# eth_part.net
KiCad netlist of a schematic drawn in Altium Designer
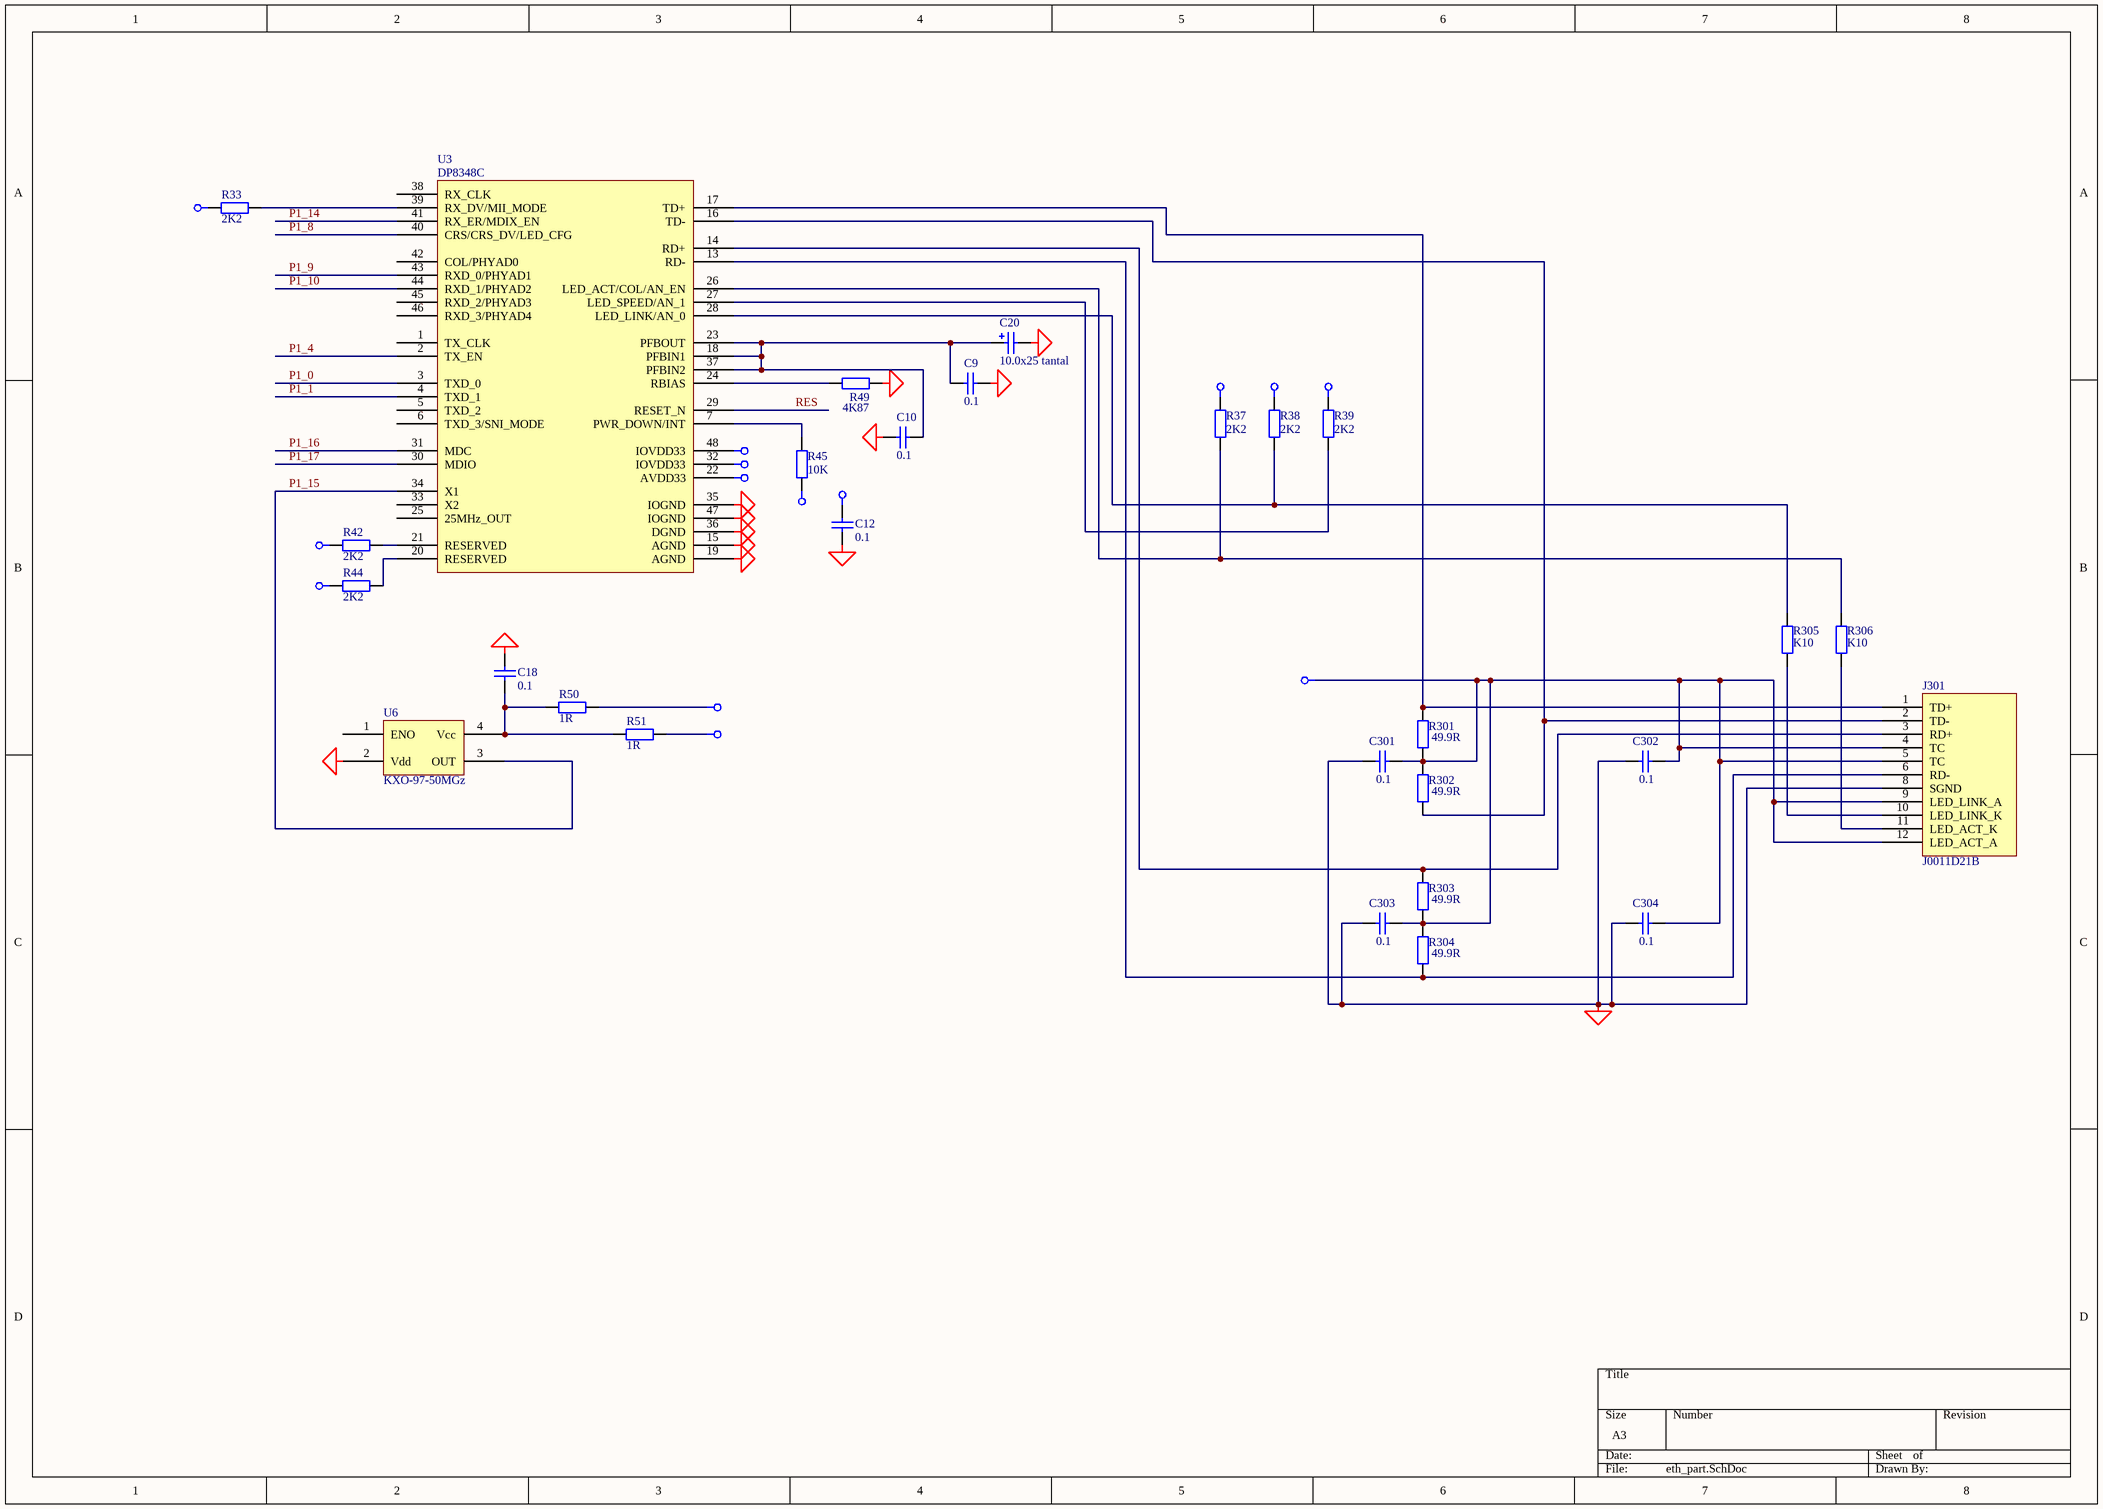
[diagram p0: eth_part.SchDoc]

(export (version "E")
  (design (tool "Eeschema 10.0.6"))
  (components
    (comp (ref "C9")
      (value "0.1")
      (footprint "C3216-1206")
      (description "Capacitor (Semiconductor SIM Model)")
      (fields (field (name "MANUFACTURER") "Generic Components") (field (name "PUBLISHER") "Altium Limited"))
      (libsource (lib "Miscellaneous Devices") (part "Cap Semi"))
    )
    (comp (ref "C10")
      (value "0.1")
      (footprint "C3216-1206")
      (description "Capacitor (Semiconductor SIM Model)")
      (fields (field (name "MANUFACTURER") "Generic Components") (field (name "PUBLISHER") "Altium Limited"))
      (libsource (lib "Miscellaneous Devices") (part "Cap Semi"))
    )
    (comp (ref "C12")
      (value "0.1")
      (footprint "_1206")
      (description "Capacitor (Semiconductor SIM Model)")
      (fields (field (name "MANUFACTURER") "Generic Components") (field (name "PUBLISHER") "Altium Limited"))
      (libsource (lib "Miscellaneous Devices") (part "Cap Semi"))
    )
    (comp (ref "C18")
      (value "0.1")
      (footprint "_1206")
      (description "Capacitor (Semiconductor SIM Model)")
      (fields (field (name "MANUFACTURER") "Generic Components") (field (name "PUBLISHER") "Altium Limited"))
      (libsource (lib "Miscellaneous Devices") (part "Cap Semi"))
    )
    (comp (ref "C20")
      (value "10.0x25 tantal")
      (footprint "CAP_EL_6_3")
      (description "Polarized Capacitor (Radial)")
      (fields (field (name "MANUFACTURER") "Generic Components") (field (name "PUBLISHER") "Altium Limited"))
      (libsource (lib "PAL") (part "Cap Pol1"))
    )
    (comp (ref "C301")
      (value "0.1")
      (footprint "C3216-1206")
      (description "Capacitor (Semiconductor SIM Model)")
      (fields (field (name "MANUFACTURER") "Generic Components") (field (name "PUBLISHER") "Altium Limited"))
      (libsource (lib "Miscellaneous Devices") (part "Cap Semi"))
    )
    (comp (ref "C302")
      (value "0.1")
      (footprint "C3216-1206")
      (description "Capacitor (Semiconductor SIM Model)")
      (fields (field (name "MANUFACTURER") "Generic Components") (field (name "PUBLISHER") "Altium Limited"))
      (libsource (lib "Miscellaneous Devices") (part "Cap Semi"))
    )
    (comp (ref "C303")
      (value "0.1")
      (footprint "C3216-1206")
      (description "Capacitor (Semiconductor SIM Model)")
      (fields (field (name "MANUFACTURER") "Generic Components") (field (name "PUBLISHER") "Altium Limited"))
      (libsource (lib "Miscellaneous Devices") (part "Cap Semi"))
    )
    (comp (ref "C304")
      (value "0.1")
      (footprint "C3216-1206")
      (description "Capacitor (Semiconductor SIM Model)")
      (fields (field (name "MANUFACTURER") "Generic Components") (field (name "PUBLISHER") "Altium Limited"))
      (libsource (lib "Miscellaneous Devices") (part "Cap Semi"))
    )
    (comp (ref "J301") (value "J0011D21B") (footprint "J0011D21B") (libsource (lib "PAL") (part "J0011D21B")))
    (comp (ref "R33")
      (value "2K2")
      (footprint "_1206")
      (description "Resistor")
      (fields (field (name "MANUFACTURER") "Generic Components") (field (name "PUBLISHER") "Altium Limited"))
      (libsource (lib "") (part "Res2_1"))
    )
    (comp (ref "R37")
      (value "2K2")
      (footprint "_1206")
      (description "Resistor")
      (fields (field (name "MANUFACTURER") "Generic Components") (field (name "PUBLISHER") "Altium Limited"))
      (libsource (lib "") (part "Res2_2"))
    )
    (comp (ref "R38")
      (value "2K2")
      (footprint "_1206")
      (description "Resistor")
      (fields (field (name "MANUFACTURER") "Generic Components") (field (name "PUBLISHER") "Altium Limited"))
      (libsource (lib "") (part "Res2_2"))
    )
    (comp (ref "R39")
      (value "2K2")
      (footprint "_1206")
      (description "Resistor")
      (fields (field (name "MANUFACTURER") "Generic Components") (field (name "PUBLISHER") "Altium Limited"))
      (libsource (lib "") (part "Res2_2"))
    )
    (comp (ref "R42")
      (value "2K2")
      (footprint "_1206")
      (description "Resistor")
      (fields (field (name "MANUFACTURER") "Generic Components") (field (name "PUBLISHER") "Altium Limited"))
      (libsource (lib "") (part "Res2_1"))
    )
    (comp (ref "R44")
      (value "2K2")
      (footprint "_1206")
      (description "Resistor")
      (fields (field (name "MANUFACTURER") "Generic Components") (field (name "PUBLISHER") "Altium Limited"))
      (libsource (lib "") (part "Res2_1"))
    )
    (comp (ref "R45")
      (value "10K")
      (footprint "_1206")
      (description "Resistor")
      (fields (field (name "MANUFACTURER") "Generic Components") (field (name "PUBLISHER") "Altium Limited"))
      (libsource (lib "Miscellaneous Devices") (part "Res2"))
    )
    (comp (ref "R49")
      (value "4K87")
      (footprint "_1206")
      (description "Resistor")
      (fields (field (name "MANUFACTURER") "Generic Components") (field (name "PUBLISHER") "Altium Limited"))
      (libsource (lib "") (part "Res2_1"))
    )
    (comp (ref "R50")
      (value "1R")
      (footprint "_1206")
      (description "Resistor")
      (fields (field (name "MANUFACTURER") "Generic Components") (field (name "PUBLISHER") "Altium Limited"))
      (libsource (lib "") (part "Res2_3"))
    )
    (comp (ref "R51")
      (value "1R")
      (footprint "_1206")
      (description "Resistor")
      (fields (field (name "MANUFACTURER") "Generic Components") (field (name "PUBLISHER") "Altium Limited"))
      (libsource (lib "") (part "Res2_3"))
    )
    (comp (ref "R301")
      (value "49.9R")
      (footprint "_1206")
      (description "Resistor")
      (fields (field (name "MANUFACTURER") "Generic Components") (field (name "PUBLISHER") "Altium Limited"))
      (libsource (lib "Miscellaneous Devices") (part "Res2"))
    )
    (comp (ref "R302")
      (value "49.9R")
      (footprint "_1206")
      (description "Resistor")
      (fields (field (name "MANUFACTURER") "Generic Components") (field (name "PUBLISHER") "Altium Limited"))
      (libsource (lib "Miscellaneous Devices") (part "Res2"))
    )
    (comp (ref "R303")
      (value "49.9R")
      (footprint "_1206")
      (description "Resistor")
      (fields (field (name "MANUFACTURER") "Generic Components") (field (name "PUBLISHER") "Altium Limited"))
      (libsource (lib "Miscellaneous Devices") (part "Res2"))
    )
    (comp (ref "R304")
      (value "49.9R")
      (footprint "_1206")
      (description "Resistor")
      (fields (field (name "MANUFACTURER") "Generic Components") (field (name "PUBLISHER") "Altium Limited"))
      (libsource (lib "Miscellaneous Devices") (part "Res2"))
    )
    (comp (ref "R305")
      (value "K10")
      (footprint "_1206")
      (description "Resistor")
      (fields (field (name "MANUFACTURER") "Generic Components") (field (name "PUBLISHER") "Altium Limited"))
      (libsource (lib "") (part "Res2_2"))
    )
    (comp (ref "R306")
      (value "K10")
      (footprint "_1206")
      (description "Resistor")
      (fields (field (name "MANUFACTURER") "Generic Components") (field (name "PUBLISHER") "Altium Limited"))
      (libsource (lib "") (part "Res2_2"))
    )
    (comp (ref "U3") (value "DP8348C") (footprint "F-QFP7X7-G48/N") (libsource (lib "PAL") (part "DP8348C")))
    (comp (ref "U6") (value "KXO-97-50MGz") (footprint "KXO-97") (libsource (lib "PAL") (part "KXO-97")))
  )
  (nets
    (net (code "1") (name "+3v3") (class "Default")
      (node (ref "C12") (pin "1") (pinfunction "1_1") (pintype "passive"))
      (node (ref "C301") (pin "2") (pinfunction "2_2") (pintype "passive"))
      (node (ref "C302") (pin "2") (pinfunction "2_2") (pintype "passive"))
      (node (ref "C303") (pin "2") (pinfunction "2_2") (pintype "passive"))
      (node (ref "C304") (pin "2") (pinfunction "2_2") (pintype "passive"))
      (node (ref "J301") (pin "12") (pinfunction "LED_ACT_A_12") (pintype "passive"))
      (node (ref "J301") (pin "4") (pinfunction "TC_4") (pintype "passive"))
      (node (ref "J301") (pin "5") (pinfunction "TC_5") (pintype "passive"))
      (node (ref "J301") (pin "9") (pinfunction "LED_LINK_A_9") (pintype "passive"))
      (node (ref "R301") (pin "2") (pinfunction "2_2") (pintype "passive"))
      (node (ref "R302") (pin "1") (pinfunction "1_1") (pintype "passive"))
      (node (ref "R303") (pin "2") (pinfunction "2_2") (pintype "passive"))
      (node (ref "R304") (pin "1") (pinfunction "1_1") (pintype "passive"))
      (node (ref "R33") (pin "2") (pinfunction "2_2") (pintype "passive"))
      (node (ref "R37") (pin "2") (pinfunction "2_2") (pintype "passive"))
      (node (ref "R38") (pin "2") (pinfunction "2_2") (pintype "passive"))
      (node (ref "R39") (pin "2") (pinfunction "2_2") (pintype "passive"))
      (node (ref "R42") (pin "2") (pinfunction "2_2") (pintype "passive"))
      (node (ref "R44") (pin "2") (pinfunction "2_2") (pintype "passive"))
      (node (ref "R45") (pin "2") (pinfunction "2_2") (pintype "passive"))
      (node (ref "R51") (pin "2") (pinfunction "2_2") (pintype "passive"))
      (node (ref "U3") (pin "22") (pinfunction "AVDD33_22") (pintype "passive"))
      (node (ref "U3") (pin "32") (pinfunction "IOVDD33_32") (pintype "passive"))
      (node (ref "U3") (pin "48") (pinfunction "IOVDD33_48") (pintype "passive"))
    )
    (net (code "2") (name "+5v") (class "Default")
      (node (ref "R50") (pin "2") (pinfunction "2_2") (pintype "passive"))
    )
    (net (code "3") (name "/P1_0") (class "Default")
      (node (ref "U3") (pin "3") (pinfunction "TXD_0_3") (pintype "passive"))
    )
    (net (code "4") (name "/P1_1") (class "Default")
      (node (ref "U3") (pin "4") (pinfunction "TXD_1_4") (pintype "passive"))
    )
    (net (code "5") (name "/P1_4") (class "Default")
      (node (ref "U3") (pin "2") (pinfunction "TX_EN_2") (pintype "passive"))
    )
    (net (code "6") (name "/P1_8") (class "Default")
      (node (ref "U3") (pin "40") (pinfunction "CRS/CRS_DV/LED_CFG_40") (pintype "passive"))
    )
    (net (code "7") (name "/P1_9") (class "Default")
      (node (ref "U3") (pin "43") (pinfunction "RXD_0/PHYAD1_43") (pintype "passive"))
    )
    (net (code "8") (name "/P1_10") (class "Default")
      (node (ref "U3") (pin "44") (pinfunction "RXD_1/PHYAD2_44") (pintype "passive"))
    )
    (net (code "9") (name "/P1_14") (class "Default")
      (node (ref "U3") (pin "41") (pinfunction "RX_ER/MDIX_EN_41") (pintype "passive"))
    )
    (net (code "10") (name "/P1_15") (class "Default")
      (node (ref "U3") (pin "34") (pinfunction "X1_34") (pintype "passive"))
      (node (ref "U6") (pin "3") (pinfunction "OUT_3") (pintype "passive"))
    )
    (net (code "11") (name "/P1_16") (class "Default")
      (node (ref "U3") (pin "31") (pinfunction "MDC_31") (pintype "passive"))
    )
    (net (code "12") (name "/P1_17") (class "Default")
      (node (ref "U3") (pin "30") (pinfunction "MDIO_30") (pintype "passive"))
    )
    (net (code "13") (name "/RES") (class "Default")
      (node (ref "U3") (pin "29") (pinfunction "RESET_N_29") (pintype "passive"))
    )
    (net (code "14") (name "GND") (class "Default")
      (node (ref "C10") (pin "2") (pinfunction "2_2") (pintype "passive"))
      (node (ref "C12") (pin "2") (pinfunction "2_2") (pintype "passive"))
      (node (ref "C18") (pin "2") (pinfunction "2_2") (pintype "passive"))
      (node (ref "C20") (pin "2") (pinfunction "2_2") (pintype "passive"))
      (node (ref "C301") (pin "1") (pinfunction "1_1") (pintype "passive"))
      (node (ref "C302") (pin "1") (pinfunction "1_1") (pintype "passive"))
      (node (ref "C303") (pin "1") (pinfunction "1_1") (pintype "passive"))
      (node (ref "C304") (pin "1") (pinfunction "1_1") (pintype "passive"))
      (node (ref "C9") (pin "2") (pinfunction "2_2") (pintype "passive"))
      (node (ref "J301") (pin "8") (pinfunction "SGND_8") (pintype "passive"))
      (node (ref "R49") (pin "1") (pinfunction "1_1") (pintype "passive"))
      (node (ref "U3") (pin "15") (pinfunction "AGND_15") (pintype "passive"))
      (node (ref "U3") (pin "19") (pinfunction "AGND_19") (pintype "passive"))
      (node (ref "U3") (pin "35") (pinfunction "IOGND_35") (pintype "passive"))
      (node (ref "U3") (pin "36") (pinfunction "DGND_36") (pintype "passive"))
      (node (ref "U3") (pin "47") (pinfunction "IOGND_47") (pintype "passive"))
      (node (ref "U6") (pin "2") (pinfunction "Vdd_2") (pintype "passive"))
    )
    (net (code "15") (name "Net-(J301-LED_ACT_K)") (class "Default")
      (node (ref "J301") (pin "11") (pinfunction "LED_ACT_K_11") (pintype "passive"))
      (node (ref "R306") (pin "1") (pinfunction "1_1") (pintype "passive"))
    )
    (net (code "16") (name "Net-(J301-LED_LINK_K)") (class "Default")
      (node (ref "J301") (pin "10") (pinfunction "LED_LINK_K_10") (pintype "passive"))
      (node (ref "R305") (pin "1") (pinfunction "1_1") (pintype "passive"))
    )
    (net (code "17") (name "Net-(J301-RD+)") (class "Default")
      (node (ref "J301") (pin "3") (pinfunction "RD+_3") (pintype "passive"))
      (node (ref "R303") (pin "1") (pinfunction "1_1") (pintype "passive"))
      (node (ref "U3") (pin "14") (pinfunction "RD+_14") (pintype "passive"))
    )
    (net (code "18") (name "Net-(J301-RD-)") (class "Default")
      (node (ref "J301") (pin "6") (pinfunction "RD-_6") (pintype "passive"))
      (node (ref "R304") (pin "2") (pinfunction "2_2") (pintype "passive"))
      (node (ref "U3") (pin "13") (pinfunction "RD-_13") (pintype "passive"))
    )
    (net (code "19") (name "Net-(J301-TD+)") (class "Default")
      (node (ref "J301") (pin "1") (pinfunction "TD+_1") (pintype "passive"))
      (node (ref "R301") (pin "1") (pinfunction "1_1") (pintype "passive"))
      (node (ref "U3") (pin "17") (pinfunction "TD+_17") (pintype "passive"))
    )
    (net (code "20") (name "Net-(J301-TD-)") (class "Default")
      (node (ref "J301") (pin "2") (pinfunction "TD-_2") (pintype "passive"))
      (node (ref "R302") (pin "2") (pinfunction "2_2") (pintype "passive"))
      (node (ref "U3") (pin "16") (pinfunction "TD-_16") (pintype "passive"))
    )
    (net (code "21") (name "Net-(R42-Pad1)") (class "Default")
      (node (ref "R42") (pin "1") (pinfunction "1_1") (pintype "passive"))
      (node (ref "U3") (pin "21") (pinfunction "RESERVED_21") (pintype "passive"))
    )
    (net (code "22") (name "Net-(R44-Pad1)") (class "Default")
      (node (ref "R44") (pin "1") (pinfunction "1_1") (pintype "passive"))
      (node (ref "U3") (pin "20") (pinfunction "RESERVED_20") (pintype "passive"))
    )
    (net (code "23") (name "Net-(U3-LED_ACT{slash}COL{slash}AN_EN)") (class "Default")
      (node (ref "R306") (pin "2") (pinfunction "2_2") (pintype "passive"))
      (node (ref "R37") (pin "1") (pinfunction "1_1") (pintype "passive"))
      (node (ref "U3") (pin "26") (pinfunction "LED_ACT/COL/AN_EN_26") (pintype "passive"))
    )
    (net (code "24") (name "Net-(U3-LED_LINK{slash}AN_0)") (class "Default")
      (node (ref "R305") (pin "2") (pinfunction "2_2") (pintype "passive"))
      (node (ref "R38") (pin "1") (pinfunction "1_1") (pintype "passive"))
      (node (ref "U3") (pin "28") (pinfunction "LED_LINK/AN_0_28") (pintype "passive"))
    )
    (net (code "25") (name "Net-(U3-LED_SPEED{slash}AN_1)") (class "Default")
      (node (ref "R39") (pin "1") (pinfunction "1_1") (pintype "passive"))
      (node (ref "U3") (pin "27") (pinfunction "LED_SPEED/AN_1_27") (pintype "passive"))
    )
    (net (code "26") (name "Net-(U3-PFBIN1)") (class "Default")
      (node (ref "C10") (pin "1") (pinfunction "1_1") (pintype "passive"))
      (node (ref "C20") (pin "1") (pinfunction "1_1") (pintype "passive"))
      (node (ref "C9") (pin "1") (pinfunction "1_1") (pintype "passive"))
      (node (ref "U3") (pin "18") (pinfunction "PFBIN1_18") (pintype "passive"))
      (node (ref "U3") (pin "23") (pinfunction "PFBOUT_23") (pintype "passive"))
      (node (ref "U3") (pin "37") (pinfunction "PFBIN2_37") (pintype "passive"))
    )
    (net (code "27") (name "Net-(U3-PWR_DOWN{slash}INT)") (class "Default")
      (node (ref "R45") (pin "1") (pinfunction "1_1") (pintype "passive"))
      (node (ref "U3") (pin "7") (pinfunction "PWR_DOWN/INT_7") (pintype "passive"))
    )
    (net (code "28") (name "Net-(U3-RBIAS)") (class "Default")
      (node (ref "R49") (pin "2") (pinfunction "2_2") (pintype "passive"))
      (node (ref "U3") (pin "24") (pinfunction "RBIAS_24") (pintype "passive"))
    )
    (net (code "29") (name "Net-(U3-RX_DV{slash}MII_MODE)") (class "Default")
      (node (ref "R33") (pin "1") (pinfunction "1_1") (pintype "passive"))
      (node (ref "U3") (pin "39") (pinfunction "RX_DV/MII_MODE_39") (pintype "passive"))
    )
    (net (code "30") (name "Net-(U6-Vcc)") (class "Default")
      (node (ref "C18") (pin "1") (pinfunction "1_1") (pintype "passive"))
      (node (ref "R50") (pin "1") (pinfunction "1_1") (pintype "passive"))
      (node (ref "R51") (pin "1") (pinfunction "1_1") (pintype "passive"))
      (node (ref "U6") (pin "4") (pinfunction "Vcc_4") (pintype "passive"))
    )
    (net (code "31") (name "unconnected-(U3-25MHz_OUT-Pad25)") (class "Default")
      (node (ref "U3") (pin "25") (pinfunction "25MHz_OUT_25") (pintype "passive"))
    )
    (net (code "32") (name "unconnected-(U3-COL{slash}PHYAD0-Pad42)") (class "Default")
      (node (ref "U3") (pin "42") (pinfunction "COL/PHYAD0_42") (pintype "passive"))
    )
    (net (code "33") (name "unconnected-(U3-RXD_2{slash}PHYAD3-Pad45)") (class "Default")
      (node (ref "U3") (pin "45") (pinfunction "RXD_2/PHYAD3_45") (pintype "passive"))
    )
    (net (code "34") (name "unconnected-(U3-RXD_3{slash}PHYAD4-Pad46)") (class "Default")
      (node (ref "U3") (pin "46") (pinfunction "RXD_3/PHYAD4_46") (pintype "passive"))
    )
    (net (code "35") (name "unconnected-(U3-RX_CLK-Pad38)") (class "Default")
      (node (ref "U3") (pin "38") (pinfunction "RX_CLK_38") (pintype "passive"))
    )
    (net (code "36") (name "unconnected-(U3-TXD_2-Pad5)") (class "Default")
      (node (ref "U3") (pin "5") (pinfunction "TXD_2_5") (pintype "passive"))
    )
    (net (code "37") (name "unconnected-(U3-TXD_3{slash}SNI_MODE-Pad6)") (class "Default")
      (node (ref "U3") (pin "6") (pinfunction "TXD_3/SNI_MODE_6") (pintype "passive"))
    )
    (net (code "38") (name "unconnected-(U3-TX_CLK-Pad1)") (class "Default")
      (node (ref "U3") (pin "1") (pinfunction "TX_CLK_1") (pintype "passive"))
    )
    (net (code "39") (name "unconnected-(U3-X2-Pad33)") (class "Default")
      (node (ref "U3") (pin "33") (pinfunction "X2_33") (pintype "passive"))
    )
    (net (code "40") (name "unconnected-(U6-ENO-Pad1)") (class "Default")
      (node (ref "U6") (pin "1") (pinfunction "ENO_1") (pintype "passive"))
    )
  )
)
